# STM32C011F6U.net
KiCad netlist of a schematic drawn in Altium Designer
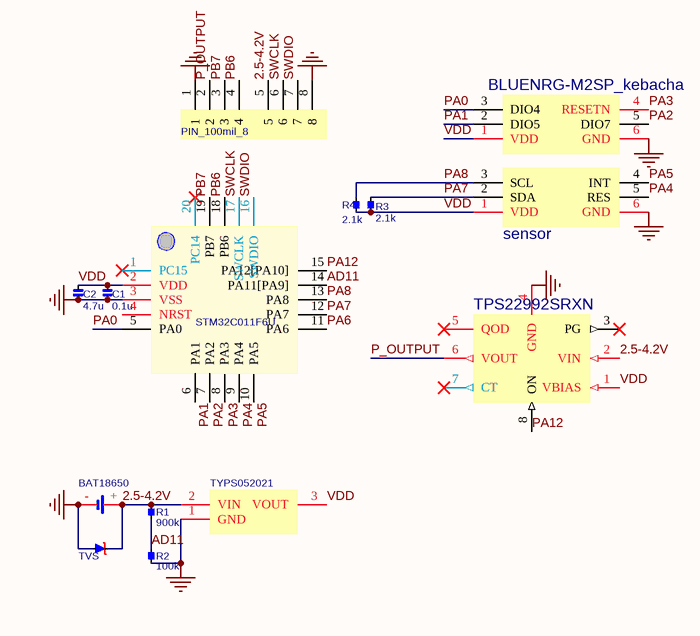
[diagram p0: STM32C011F6U.SchDoc]

(export (version "E")
  (design (tool "Eeschema 10.0.6"))
  (components
    (comp (ref "BAT18650")
      (value "~")
      (description "4.2 to 2.5V")
      (libsource (lib "altium-import") (part "root_2_BAT18650_"))
    )
    (comp (ref "BLUENRG-M2SP_kebacha")
      (value "~")
      (libsource (lib "altium-import") (part "root_0_BLUENRG-M2SP_kebacha_"))
    )
    (comp (ref "C1") (value "0.1u") (footprint "0805") (libsource (lib "altium-import") (part "root_3_C_")))
    (comp (ref "C2") (value "4.7u") (footprint "0805") (libsource (lib "altium-import") (part "root_3_C_")))
    (comp (ref "PIN_100mil_8")
      (value "~")
      (libsource (lib "altium-import") (part "root_1_mirrored_PIN_100mil__"))
    )
    (comp (ref "R1") (value "900k") (footprint "0805") (libsource (lib "altium-import") (part "root_1_R_")))
    (comp (ref "R2") (value "100k") (footprint "0805") (libsource (lib "altium-import") (part "root_1_R_")))
    (comp (ref "R3") (value "2.1k") (footprint "0805") (libsource (lib "altium-import") (part "root_3_R_")))
    (comp (ref "R4") (value "2.1k") (footprint "0805") (libsource (lib "altium-import") (part "root_3_R_")))
    (comp (ref "sensor") (value "~") (libsource (lib "altium-import") (part "root_0_sensor_")))
    (comp (ref "STM32C011F6U")
      (value "~")
      (footprint "UFQFPN20")
      (libsource (lib "altium-import") (part "root_0_STM32C011F6U_"))
    )
    (comp (ref "TPS22992SRXN") (value "~") (libsource (lib "altium-import") (part "root_2_TPS22992SRXN_")))
    (comp (ref "TVS")
      (value "SMF5.0A")
      (footprint "SMF")
      (libsource (lib "altium-import") (part "root_2_TVS_"))
    )
    (comp (ref "TYPS052021") (value "LDO") (libsource (lib "STM32C011F6U") (part "LDO")))
  )
  (nets
    (net (code "1") (name "/2.5-4.2V") (class "Default")
      (node (ref "BAT18650") (pin "+") (pintype "passive"))
      (node (ref "PIN_100mil_8") (pin "5") (pinfunction "5_5") (pintype "passive"))
      (node (ref "R1") (pin "2") (pinfunction "2_2") (pintype "passive"))
      (node (ref "TPS22992SRXN") (pin "2") (pinfunction "VIN_2") (pintype "input"))
      (node (ref "TVS") (pin "2") (pintype "passive"))
      (node (ref "TYPS052021") (pin "2") (pinfunction "VIN_2") (pintype "passive"))
    )
    (net (code "2") (name "/AD11") (class "Default")
      (node (ref "R1") (pin "1") (pinfunction "1_1") (pintype "passive"))
      (node (ref "R2") (pin "2") (pinfunction "2_2") (pintype "passive"))
      (node (ref "STM32C011F6U") (pin "14") (pinfunction "PA11[PA9]_14") (pintype "passive"))
    )
    (net (code "3") (name "/PA0") (class "Default")
      (node (ref "BLUENRG-M2SP_kebacha") (pin "3") (pinfunction "DIO4_3") (pintype "passive"))
      (node (ref "STM32C011F6U") (pin "5") (pinfunction "PA0_5") (pintype "passive"))
    )
    (net (code "4") (name "/PA1") (class "Default")
      (node (ref "BLUENRG-M2SP_kebacha") (pin "2") (pinfunction "DIO5_2") (pintype "passive"))
      (node (ref "STM32C011F6U") (pin "6") (pinfunction "PA1_6") (pintype "passive"))
    )
    (net (code "5") (name "/PA2") (class "Default")
      (node (ref "BLUENRG-M2SP_kebacha") (pin "5") (pinfunction "DIO7_5") (pintype "passive"))
      (node (ref "STM32C011F6U") (pin "7") (pinfunction "PA2_7") (pintype "passive"))
    )
    (net (code "6") (name "/PA3") (class "Default")
      (node (ref "BLUENRG-M2SP_kebacha") (pin "4") (pinfunction "RESETN_4") (pintype "passive"))
      (node (ref "STM32C011F6U") (pin "8") (pinfunction "PA3_8") (pintype "passive"))
    )
    (net (code "7") (name "/PA4") (class "Default")
      (node (ref "STM32C011F6U") (pin "9") (pinfunction "PA4_9") (pintype "passive"))
      (node (ref "sensor") (pin "5") (pinfunction "RES_5") (pintype "passive"))
    )
    (net (code "8") (name "/PA5") (class "Default")
      (node (ref "STM32C011F6U") (pin "10") (pinfunction "PA5_10") (pintype "power_in"))
      (node (ref "sensor") (pin "4") (pinfunction "INT_4") (pintype "passive"))
    )
    (net (code "9") (name "/PA6") (class "Default")
      (node (ref "STM32C011F6U") (pin "11") (pinfunction "PA6_11") (pintype "passive"))
    )
    (net (code "10") (name "/PA7") (class "Default")
      (node (ref "R3") (pin "1") (pinfunction "1_1") (pintype "passive"))
      (node (ref "STM32C011F6U") (pin "12") (pinfunction "PA7_12") (pintype "passive"))
      (node (ref "sensor") (pin "2") (pinfunction "SDA_2") (pintype "passive"))
    )
    (net (code "11") (name "/PA8") (class "Default")
      (node (ref "R4") (pin "1") (pinfunction "1_1") (pintype "passive"))
      (node (ref "STM32C011F6U") (pin "13") (pinfunction "PA8_13") (pintype "passive"))
      (node (ref "sensor") (pin "3") (pinfunction "SCL_3") (pintype "passive"))
    )
    (net (code "12") (name "/PA12") (class "Default")
      (node (ref "STM32C011F6U") (pin "15") (pinfunction "PA12[PA10]_15") (pintype "passive"))
      (node (ref "TPS22992SRXN") (pin "8") (pinfunction "ON_8") (pintype "input"))
    )
    (net (code "13") (name "/PB6") (class "Default")
      (node (ref "PIN_100mil_8") (pin "4") (pinfunction "4_4") (pintype "passive"))
      (node (ref "STM32C011F6U") (pin "18") (pinfunction "PB6_18") (pintype "passive"))
    )
    (net (code "14") (name "/PB7") (class "Default")
      (node (ref "PIN_100mil_8") (pin "3") (pinfunction "3_3") (pintype "passive"))
      (node (ref "STM32C011F6U") (pin "19") (pinfunction "PB7_19") (pintype "passive"))
    )
    (net (code "15") (name "/P_OUTPUT") (class "Default")
      (node (ref "PIN_100mil_8") (pin "2") (pinfunction "2_2") (pintype "passive"))
      (node (ref "TPS22992SRXN") (pin "6") (pinfunction "VOUT_6") (pintype "output"))
    )
    (net (code "16") (name "/SWCLK") (class "Default")
      (node (ref "PIN_100mil_8") (pin "6") (pinfunction "6_6") (pintype "passive"))
      (node (ref "STM32C011F6U") (pin "17") (pinfunction "SWCLK_17") (pintype "passive"))
    )
    (net (code "17") (name "/SWDIO") (class "Default")
      (node (ref "PIN_100mil_8") (pin "7") (pinfunction "7_7") (pintype "passive"))
      (node (ref "STM32C011F6U") (pin "16") (pinfunction "SWDIO_16") (pintype "passive"))
    )
    (net (code "18") (name "/VDD") (class "Default")
      (node (ref "BLUENRG-M2SP_kebacha") (pin "1") (pinfunction "VDD_1") (pintype "passive"))
      (node (ref "C1") (pin "1") (pinfunction "1_1") (pintype "passive"))
      (node (ref "C2") (pin "1") (pinfunction "1_1") (pintype "passive"))
      (node (ref "R3") (pin "2") (pinfunction "2_2") (pintype "passive"))
      (node (ref "R4") (pin "2") (pinfunction "2_2") (pintype "passive"))
      (node (ref "STM32C011F6U") (pin "2") (pinfunction "VDD_2") (pintype "passive"))
      (node (ref "TPS22992SRXN") (pin "1") (pinfunction "VBIAS_1") (pintype "input"))
      (node (ref "TYPS052021") (pin "3") (pinfunction "VOUT_3") (pintype "passive"))
      (node (ref "sensor") (pin "1") (pinfunction "VDD_1") (pintype "passive"))
    )
    (net (code "19") (name "GND") (class "Default")
      (node (ref "BAT18650") (pin "-") (pintype "passive"))
      (node (ref "BLUENRG-M2SP_kebacha") (pin "6") (pinfunction "GND_6") (pintype "passive"))
      (node (ref "C1") (pin "2") (pinfunction "2_2") (pintype "passive"))
      (node (ref "C2") (pin "2") (pinfunction "2_2") (pintype "passive"))
      (node (ref "PIN_100mil_8") (pin "1") (pinfunction "1_1") (pintype "passive"))
      (node (ref "PIN_100mil_8") (pin "8") (pinfunction "8_8") (pintype "passive"))
      (node (ref "R2") (pin "1") (pinfunction "1_1") (pintype "passive"))
      (node (ref "STM32C011F6U") (pin "3") (pinfunction "VSS_3") (pintype "passive"))
      (node (ref "TPS22992SRXN") (pin "4") (pinfunction "GND_4") (pintype "passive"))
      (node (ref "TVS") (pin "1") (pintype "passive"))
      (node (ref "TYPS052021") (pin "1") (pinfunction "GND_1") (pintype "passive"))
      (node (ref "sensor") (pin "6") (pinfunction "GND_6") (pintype "passive"))
    )
    (net (code "20") (name "unconnected-(STM32C011F6U-NRST-Pad4)") (class "Default")
      (node (ref "STM32C011F6U") (pin "4") (pinfunction "NRST_4") (pintype "passive"))
    )
    (net (code "21") (name "unconnected-(STM32C011F6U-PC14-Pad20)") (class "Default")
      (node (ref "STM32C011F6U") (pin "20") (pinfunction "PC14_20") (pintype "passive+no_connect"))
    )
    (net (code "22") (name "unconnected-(STM32C011F6U-PC15-Pad1)") (class "Default")
      (node (ref "STM32C011F6U") (pin "1") (pinfunction "PC15_1") (pintype "passive+no_connect"))
    )
    (net (code "23") (name "unconnected-(TPS22992SRXN-CT-Pad7)") (class "Default")
      (node (ref "TPS22992SRXN") (pin "7") (pinfunction "CT_7") (pintype "output+no_connect"))
    )
    (net (code "24") (name "unconnected-(TPS22992SRXN-PG-Pad3)") (class "Default")
      (node (ref "TPS22992SRXN") (pin "3") (pinfunction "PG_3") (pintype "output+no_connect"))
    )
    (net (code "25") (name "unconnected-(TPS22992SRXN-QOD-Pad5)") (class "Default")
      (node (ref "TPS22992SRXN") (pin "5") (pinfunction "QOD_5") (pintype "passive+no_connect"))
    )
  )
)
